# board.net
KiCad netlist of a schematic drawn in EAGLE
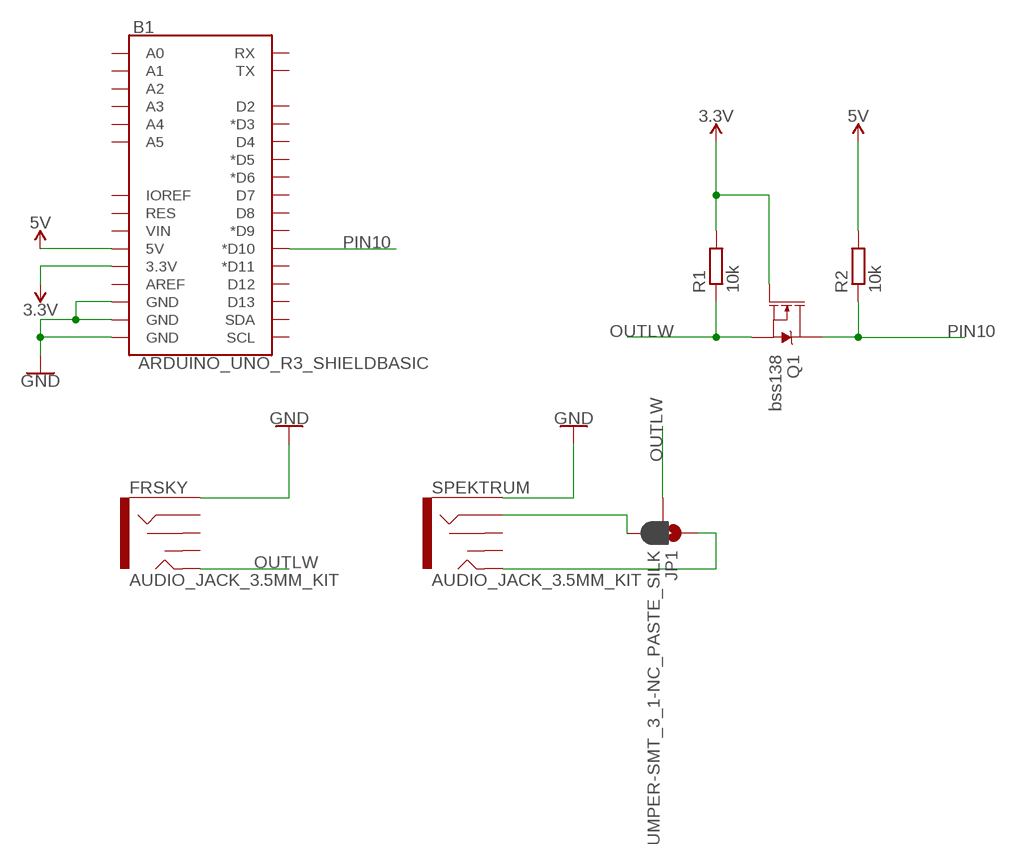
[diagram p0: schematic, sheet 1]

(export (version "E")
  (design (tool "Eeschema 10.0.6"))
  (components
    (comp (ref "B1")
      (value "ARDUINO_UNO_R3_SHIELDBASIC")
      (footprint "eagle-import:UNO_R3_SHIELD")
      (libsource (lib "eagle-import") (part "ARDUINO_UNO_R3_SHIELDBASIC"))
    )
    (comp (ref "FRSKY")
      (value "AUDIO_JACK_3.5MM_KIT")
      (footprint "eagle-import:AUDIO-JACK-KIT")
      (libsource (lib "eagle-import") (part "AUDIO_JACK_3.5MM_KIT"))
    )
    (comp (ref "JP1")
      (value "JUMPER-SMT_3_1-NC_PASTE_SILK")
      (footprint "eagle-import:SMT-JUMPER_3_1-NC_PASTE_SILK")
      (libsource (lib "eagle-import") (part "JUMPER-SMT_3_1-NC_PASTE_SILK"))
    )
    (comp (ref "Q1")
      (value "bss138")
      (footprint "eagle-import:SOT23-3")
      (libsource (lib "eagle-import") (part "MOSFET-NCH-AO3404A"))
    )
    (comp (ref "R1")
      (value "10k")
      (footprint "eagle-import:R1206")
      (libsource (lib "eagle-import") (part "R-EU_R1206"))
    )
    (comp (ref "R2")
      (value "10k")
      (footprint "eagle-import:R1206")
      (libsource (lib "eagle-import") (part "R-EU_R1206"))
    )
    (comp (ref "SPEKTRUM")
      (value "AUDIO_JACK_3.5MM_KIT")
      (footprint "eagle-import:AUDIO-JACK-KIT")
      (libsource (lib "eagle-import") (part "AUDIO_JACK_3.5MM_KIT"))
    )
  )
  (nets
    (net (code "1") (name "/OUTLW") (class "Default")
      (node (ref "FRSKY") (pin "TIP") (pinfunction "TIP_TIP") (pintype "bidirectional"))
      (node (ref "JP1") (pin "2") (pinfunction "2_2") (pintype "passive"))
      (node (ref "Q1") (pin "2") (pinfunction "S_2") (pintype "bidirectional"))
      (node (ref "R1") (pin "1") (pinfunction "1_1") (pintype "passive"))
    )
    (net (code "2") (name "/PIN10") (class "Default")
      (node (ref "B1") (pin "D10") (pinfunction "*D10_D10") (pintype "bidirectional"))
      (node (ref "Q1") (pin "3") (pinfunction "D_3") (pintype "bidirectional"))
      (node (ref "R2") (pin "1") (pinfunction "1_1") (pintype "passive"))
    )
    (net (code "3") (name "3.3V") (class "Default")
      (node (ref "B1") (pin "3.3V") (pinfunction "3.3V_3.3V") (pintype "bidirectional"))
      (node (ref "Q1") (pin "1") (pinfunction "G_1") (pintype "bidirectional"))
      (node (ref "R1") (pin "2") (pinfunction "2_2") (pintype "passive"))
    )
    (net (code "4") (name "5V") (class "Default")
      (node (ref "B1") (pin "5V") (pinfunction "5V_5V") (pintype "bidirectional"))
      (node (ref "R2") (pin "2") (pinfunction "2_2") (pintype "passive"))
    )
    (net (code "5") (name "GND") (class "Default")
      (node (ref "B1") (pin "GND@0") (pinfunction "GND_GND@0") (pintype "bidirectional"))
      (node (ref "B1") (pin "GND@1") (pinfunction "GND_GND@1") (pintype "bidirectional"))
      (node (ref "B1") (pin "GND@2") (pinfunction "GND_GND@2") (pintype "bidirectional"))
      (node (ref "FRSKY") (pin "SLEEVE") (pinfunction "SLEEVE_SLEEVE") (pintype "bidirectional"))
      (node (ref "SPEKTRUM") (pin "SLEEVE") (pinfunction "SLEEVE_SLEEVE") (pintype "bidirectional"))
    )
    (net (code "6") (name "Net-(JP1-Pad1)") (class "Default")
      (node (ref "JP1") (pin "1") (pinfunction "1_1") (pintype "passive"))
      (node (ref "SPEKTRUM") (pin "TIP") (pinfunction "TIP_TIP") (pintype "bidirectional"))
    )
    (net (code "7") (name "Net-(JP1-Pad3)") (class "Default")
      (node (ref "JP1") (pin "3") (pinfunction "3_3") (pintype "passive"))
      (node (ref "SPEKTRUM") (pin "RING") (pinfunction "RING_RING") (pintype "bidirectional"))
    )
    (net (code "8") (name "unconnected-(B1-*D3-PadD3)") (class "Default")
      (node (ref "B1") (pin "D3") (pinfunction "*D3_D3") (pintype "bidirectional"))
    )
    (net (code "9") (name "unconnected-(B1-*D5-PadD5)") (class "Default")
      (node (ref "B1") (pin "D5") (pinfunction "*D5_D5") (pintype "bidirectional"))
    )
    (net (code "10") (name "unconnected-(B1-*D6-PadD6)") (class "Default")
      (node (ref "B1") (pin "D6") (pinfunction "*D6_D6") (pintype "bidirectional"))
    )
    (net (code "11") (name "unconnected-(B1-*D9-PadD9)") (class "Default")
      (node (ref "B1") (pin "D9") (pinfunction "*D9_D9") (pintype "bidirectional"))
    )
    (net (code "12") (name "unconnected-(B1-*D11-PadD11)") (class "Default")
      (node (ref "B1") (pin "D11") (pinfunction "*D11_D11") (pintype "bidirectional"))
    )
    (net (code "13") (name "unconnected-(B1-PadA0)") (class "Default")
      (node (ref "B1") (pin "A0") (pinfunction "A0_A0") (pintype "bidirectional"))
    )
    (net (code "14") (name "unconnected-(B1-PadA1)") (class "Default")
      (node (ref "B1") (pin "A1") (pinfunction "A1_A1") (pintype "bidirectional"))
    )
    (net (code "15") (name "unconnected-(B1-PadA2)") (class "Default")
      (node (ref "B1") (pin "A2") (pinfunction "A2_A2") (pintype "bidirectional"))
    )
    (net (code "16") (name "unconnected-(B1-PadA3)") (class "Default")
      (node (ref "B1") (pin "A3") (pinfunction "A3_A3") (pintype "bidirectional"))
    )
    (net (code "17") (name "unconnected-(B1-PadA4)") (class "Default")
      (node (ref "B1") (pin "A4") (pinfunction "A4_A4") (pintype "bidirectional"))
    )
    (net (code "18") (name "unconnected-(B1-PadA5)") (class "Default")
      (node (ref "B1") (pin "A5") (pinfunction "A5_A5") (pintype "bidirectional"))
    )
    (net (code "19") (name "unconnected-(B1-PadAREF)") (class "Default")
      (node (ref "B1") (pin "AREF") (pinfunction "AREF_AREF") (pintype "bidirectional"))
    )
    (net (code "20") (name "unconnected-(B1-PadD2)") (class "Default")
      (node (ref "B1") (pin "D2") (pinfunction "D2_D2") (pintype "bidirectional"))
    )
    (net (code "21") (name "unconnected-(B1-PadD4)") (class "Default")
      (node (ref "B1") (pin "D4") (pinfunction "D4_D4") (pintype "bidirectional"))
    )
    (net (code "22") (name "unconnected-(B1-PadD7)") (class "Default")
      (node (ref "B1") (pin "D7") (pinfunction "D7_D7") (pintype "bidirectional"))
    )
    (net (code "23") (name "unconnected-(B1-PadD8)") (class "Default")
      (node (ref "B1") (pin "D8") (pinfunction "D8_D8") (pintype "bidirectional"))
    )
    (net (code "24") (name "unconnected-(B1-PadD12)") (class "Default")
      (node (ref "B1") (pin "D12") (pinfunction "D12_D12") (pintype "bidirectional"))
    )
    (net (code "25") (name "unconnected-(B1-PadD13)") (class "Default")
      (node (ref "B1") (pin "D13") (pinfunction "D13_D13") (pintype "bidirectional"))
    )
    (net (code "26") (name "unconnected-(B1-PadIOREF)") (class "Default")
      (node (ref "B1") (pin "IOREF") (pinfunction "IOREF_IOREF") (pintype "bidirectional"))
    )
    (net (code "27") (name "unconnected-(B1-PadRES)") (class "Default")
      (node (ref "B1") (pin "RES") (pinfunction "RES_RES") (pintype "bidirectional"))
    )
    (net (code "28") (name "unconnected-(B1-PadRX)") (class "Default")
      (node (ref "B1") (pin "RX") (pinfunction "RX_RX") (pintype "bidirectional"))
    )
    (net (code "29") (name "unconnected-(B1-PadSCL)") (class "Default")
      (node (ref "B1") (pin "SCL") (pinfunction "SCL_SCL") (pintype "bidirectional"))
    )
    (net (code "30") (name "unconnected-(B1-PadSDA)") (class "Default")
      (node (ref "B1") (pin "SDA") (pinfunction "SDA_SDA") (pintype "bidirectional"))
    )
    (net (code "31") (name "unconnected-(B1-PadTX)") (class "Default")
      (node (ref "B1") (pin "TX") (pinfunction "TX_TX") (pintype "bidirectional"))
    )
    (net (code "32") (name "unconnected-(B1-PadVIN)") (class "Default")
      (node (ref "B1") (pin "VIN") (pinfunction "VIN_VIN") (pintype "bidirectional"))
    )
    (net (code "33") (name "unconnected-(FRSKY-PadRING)") (class "Default")
      (node (ref "FRSKY") (pin "RING") (pinfunction "RING_RING") (pintype "bidirectional"))
    )
    (net (code "34") (name "unconnected-(FRSKY-PadRSH)") (class "Default")
      (node (ref "FRSKY") (pin "RSH") (pinfunction "RSH_RSH") (pintype "bidirectional"))
    )
    (net (code "35") (name "unconnected-(FRSKY-PadTSH)") (class "Default")
      (node (ref "FRSKY") (pin "TSH") (pinfunction "TSH_TSH") (pintype "bidirectional"))
    )
    (net (code "36") (name "unconnected-(SPEKTRUM-PadRSH)") (class "Default")
      (node (ref "SPEKTRUM") (pin "RSH") (pinfunction "RSH_RSH") (pintype "bidirectional"))
    )
    (net (code "37") (name "unconnected-(SPEKTRUM-PadTSH)") (class "Default")
      (node (ref "SPEKTRUM") (pin "TSH") (pinfunction "TSH_TSH") (pintype "bidirectional"))
    )
  )
)
